# REV04.net
KiCad netlist of a schematic drawn in Altium Designer
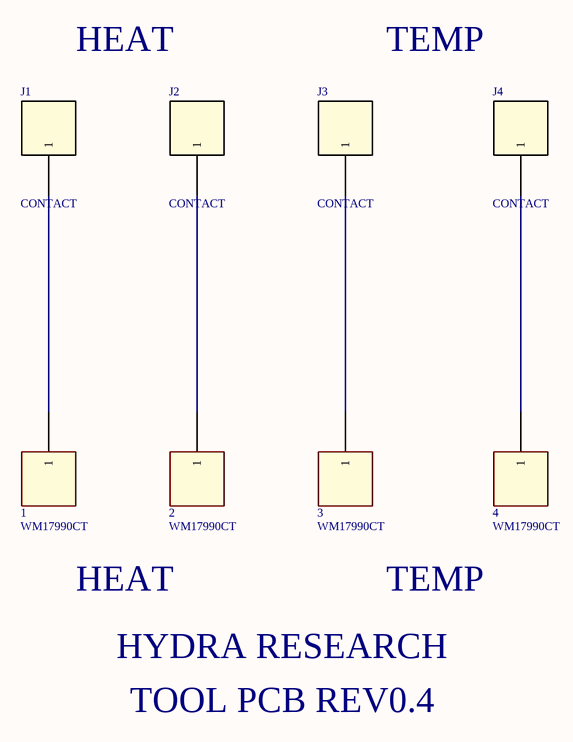
[diagram p0: REV04.SchDoc]

(export (version "E")
  (design (tool "Eeschema 10.0.6"))
  (components
    (comp (ref "1")
      (value "WM17990CT")
      (footprint "WM17990CT-ND-l")
      (fields (field (name "MPN") "WM17990CT-ND"))
      (libsource (lib "Schlib1") (part "WM17990CT"))
    )
    (comp (ref "2")
      (value "WM17990CT")
      (footprint "WM17990CT-ND-l")
      (fields (field (name "MPN") "WM17990CT-ND"))
      (libsource (lib "Schlib1") (part "WM17990CT"))
    )
    (comp (ref "3")
      (value "WM17990CT")
      (footprint "WM17990CT-ND-l")
      (fields (field (name "MPN") "WM17990CT-ND"))
      (libsource (lib "Schlib1") (part "WM17990CT"))
    )
    (comp (ref "4")
      (value "WM17990CT")
      (footprint "WM17990CT-ND-l")
      (fields (field (name "MPN") "WM17990CT-ND"))
      (libsource (lib "Schlib1") (part "WM17990CT"))
    )
    (comp (ref "J1")
      (value "CONTACT")
      (footprint "CONTRACT PAD")
      (fields (field (name "MPN") "N/C"))
      (libsource (lib "Schlib1") (part "CONTACT"))
    )
    (comp (ref "J2")
      (value "CONTACT")
      (footprint "CONTRACT PAD")
      (fields (field (name "MPN") "N/C"))
      (libsource (lib "Schlib1") (part "CONTACT"))
    )
    (comp (ref "J3")
      (value "CONTACT")
      (footprint "CONTRACT PAD")
      (fields (field (name "MPN") "N/C"))
      (libsource (lib "Schlib1") (part "CONTACT"))
    )
    (comp (ref "J4")
      (value "CONTACT")
      (footprint "CONTRACT PAD")
      (fields (field (name "MPN") "N/C"))
      (libsource (lib "Schlib1") (part "CONTACT"))
    )
  )
  (nets
    (net (code "1") (name "Net-(1-Pad1)") (class "Default")
      (node (ref "1") (pin "1") (pinfunction "1_1") (pintype "passive"))
      (node (ref "J1") (pin "1") (pinfunction "1_1") (pintype "passive"))
    )
    (net (code "2") (name "Net-(2-Pad1)") (class "Default")
      (node (ref "2") (pin "1") (pinfunction "1_1") (pintype "passive"))
      (node (ref "J2") (pin "1") (pinfunction "1_1") (pintype "passive"))
    )
    (net (code "3") (name "Net-(3-Pad1)") (class "Default")
      (node (ref "3") (pin "1") (pinfunction "1_1") (pintype "passive"))
      (node (ref "J3") (pin "1") (pinfunction "1_1") (pintype "passive"))
    )
    (net (code "4") (name "Net-(4-Pad1)") (class "Default")
      (node (ref "4") (pin "1") (pinfunction "1_1") (pintype "passive"))
      (node (ref "J4") (pin "1") (pinfunction "1_1") (pintype "passive"))
    )
  )
)
